# 1_Power.net
KiCad netlist of a schematic drawn in Altium Designer
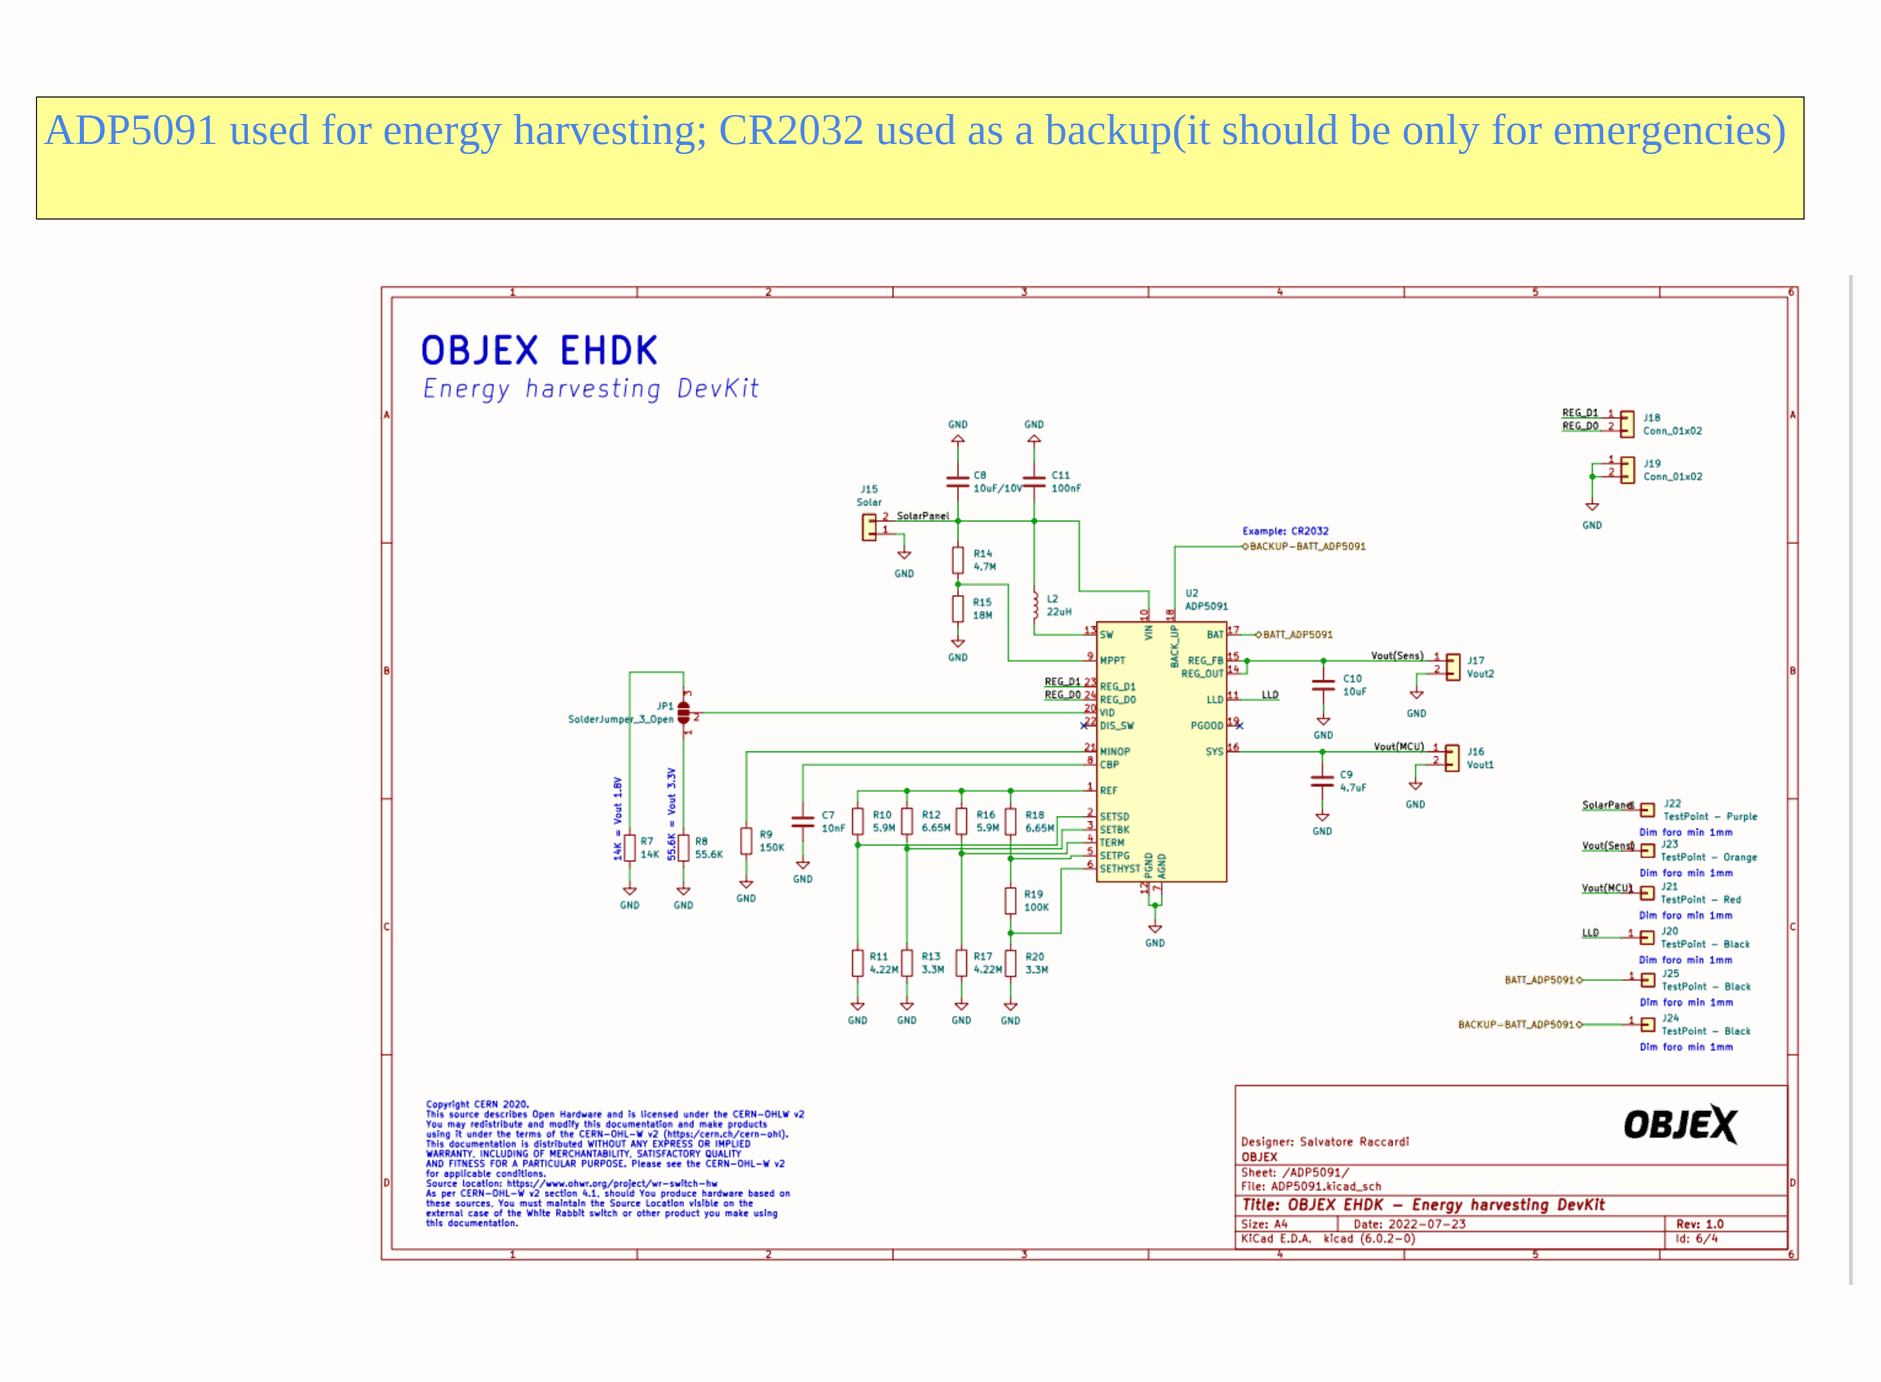
[diagram p0: 1_Power.SchDoc, left]
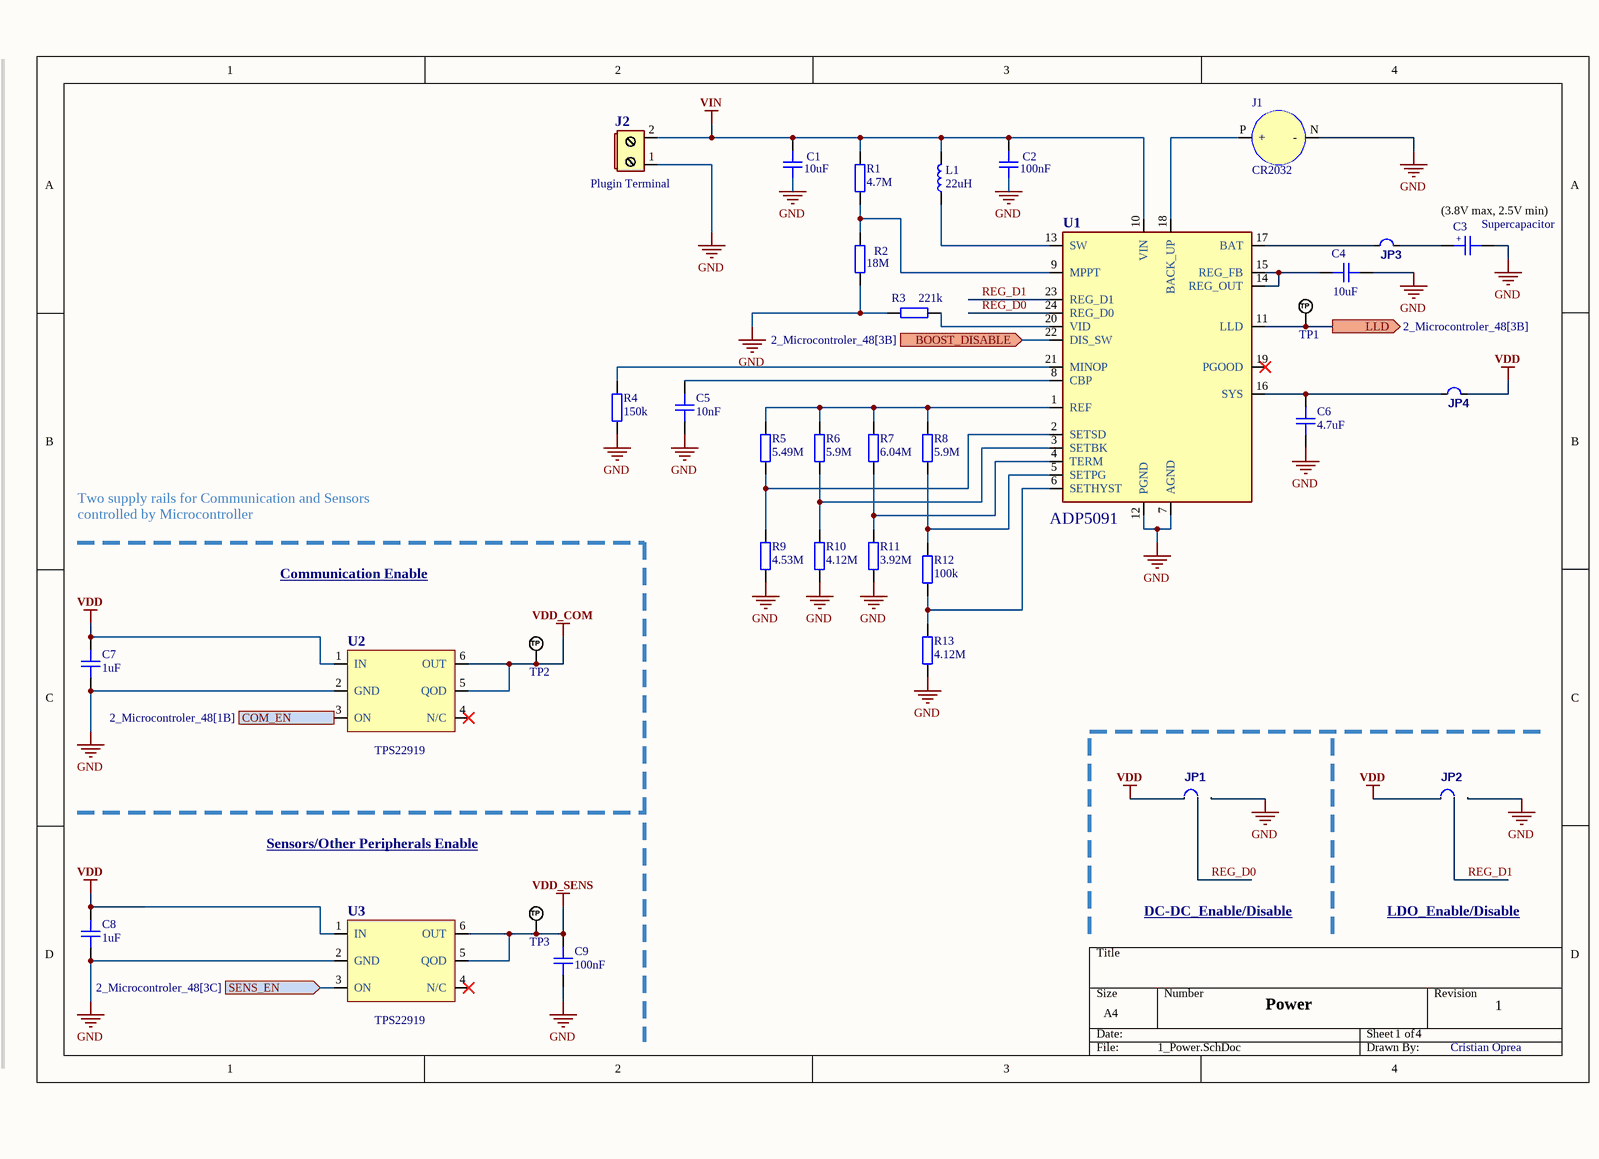
[diagram p1: 1_Power.SchDoc, middle]
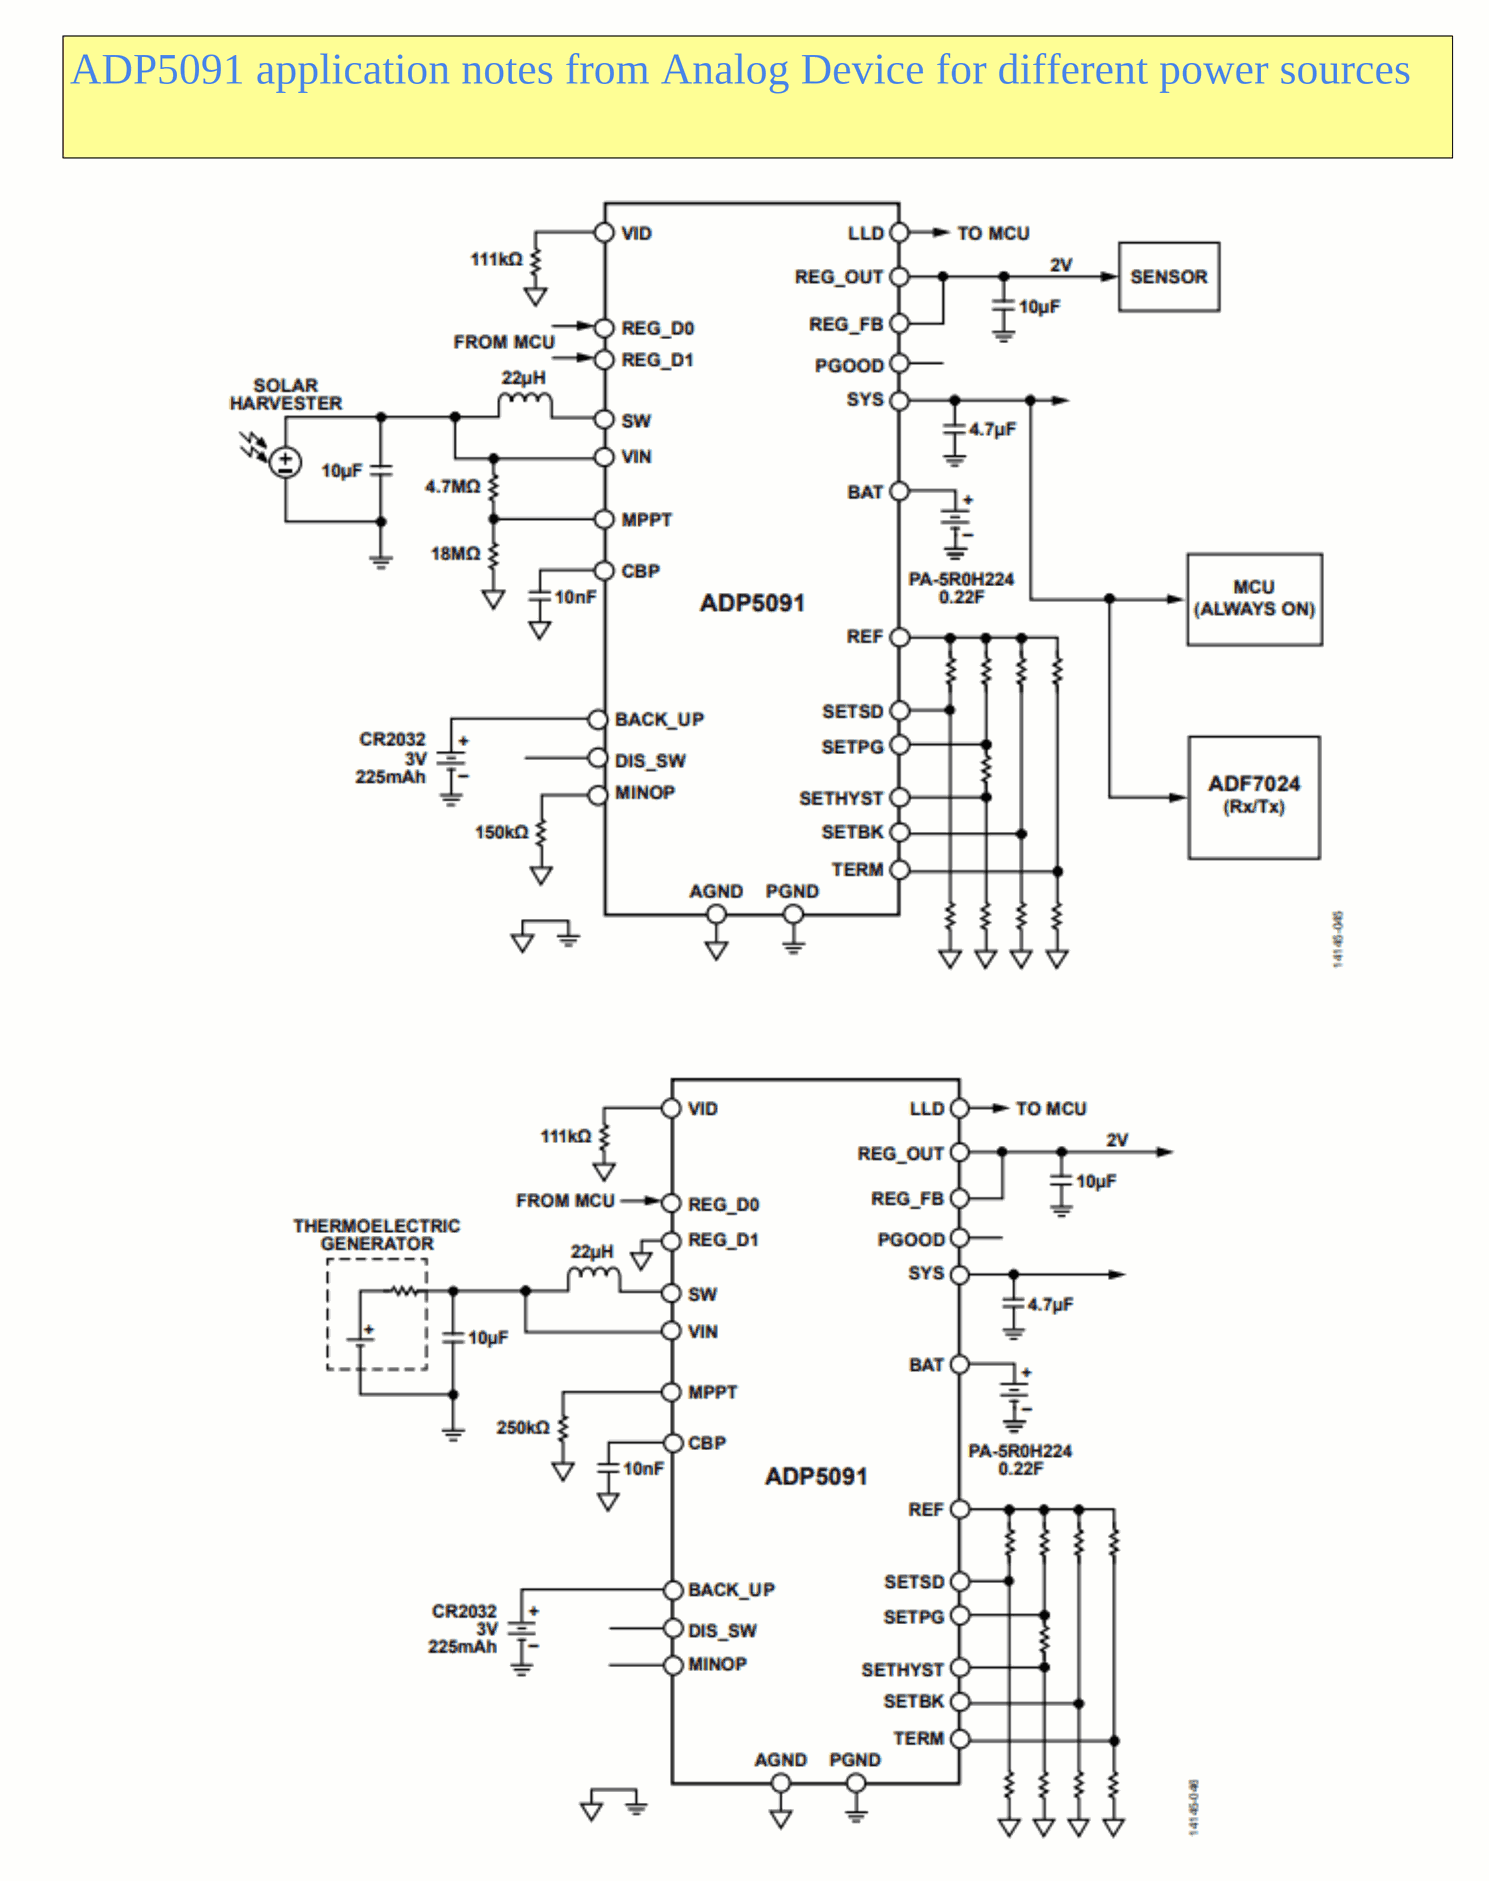
[diagram p2: 1_Power.SchDoc, right]

(export (version "E")
  (design (tool "Eeschema 10.0.6"))
  (components
    (comp (ref "C1")
      (value "10uF")
      (footprint "C0603")
      (description "Capacitor SMD 0603")
      (libsource (lib "Schlib_H2") (part "CAP_0603"))
    )
    (comp (ref "C2")
      (value "100nF")
      (footprint "C0603")
      (description "Capacitor SMD 0603")
      (libsource (lib "Schlib_H2") (part "CAP_0603"))
    )
    (comp (ref "C3")
      (value "Supercapacitor")
      (footprint "CAP_POL_8x16x3.5")
      (libsource (lib "Schlib_H2") (part "Supercapacitor"))
    )
    (comp (ref "C4")
      (value "10uF")
      (footprint "C0603")
      (description "Capacitor SMD 0603")
      (libsource (lib "Schlib_H2") (part "CAP_0603"))
    )
    (comp (ref "C5")
      (value "10nF")
      (footprint "C0603")
      (description "Capacitor SMD 0603")
      (libsource (lib "Schlib_H2") (part "CAP_0603"))
    )
    (comp (ref "C6")
      (value "4.7uF")
      (footprint "C0603")
      (description "Capacitor SMD 0603")
      (libsource (lib "Schlib_H2") (part "CAP_0603"))
    )
    (comp (ref "C7")
      (value "1uF")
      (footprint "C0603")
      (description "Capacitor SMD 0603")
      (libsource (lib "Schlib_H2") (part "CAP_0603"))
    )
    (comp (ref "C8")
      (value "1uF")
      (footprint "C0603")
      (description "Capacitor SMD 0603")
      (libsource (lib "Schlib_H2") (part "CAP_0603"))
    )
    (comp (ref "C9")
      (value "100nF")
      (footprint "C0603")
      (description "Capacitor SMD 0603")
      (libsource (lib "Schlib_H2") (part "CAP_0603"))
    )
    (comp (ref "J1")
      (value "CR2032")
      (footprint "BAT_CR2032-BS-6-1")
      (description "CR2032 Coin Cell Battery Holder")
      (fields (field (name "MANUFACTURER") "Q&J") (field (name "MANUFACTURER PART NUMBER") "CR2032-BS-6-1"))
      (libsource (lib "Schlib_H2") (part "CR2032-BS-6-1"))
    )
    (comp (ref "J2")
      (value "Plugin Terminal")
      (footprint "2.54_pluggable_terminal")
      (description "Screw terminal or plug terminal for power")
      (libsource (lib "Schlib_H2") (part "Power_Connector"))
    )
    (comp (ref "JP1")
      (value "JUMPER_3PIN")
      (footprint "HEADER_1x3_2.54")
      (libsource (lib "Schlib_H2") (part "JUMPER_3PIN"))
    )
    (comp (ref "JP2")
      (value "JUMPER_3PIN")
      (footprint "HEADER_1x3_2.54")
      (libsource (lib "Schlib_H2") (part "JUMPER_3PIN"))
    )
    (comp (ref "JP3")
      (value "JUMPER")
      (footprint "HEADER_1x2_2.54")
      (libsource (lib "Schlib_H2") (part "JUMPER"))
    )
    (comp (ref "JP4")
      (value "JUMPER")
      (footprint "HEADER_1x2_2.54")
      (libsource (lib "Schlib_H2") (part "JUMPER"))
    )
    (comp (ref "L1")
      (value "22uH")
      (footprint "IND_3.2_4")
      (description "Inductor SMD 1008")
      (libsource (lib "Schlib_H2") (part "IND_1008"))
    )
    (comp (ref "R1")
      (value "4.7M")
      (footprint "R0603")
      (description "Resistor SMD 0603")
      (libsource (lib "Schlib_H2") (part "RES_0603"))
    )
    (comp (ref "R2")
      (value "18M")
      (footprint "R0603")
      (description "Resistor SMD 0603")
      (libsource (lib "Schlib_H2") (part "RES_0603"))
    )
    (comp (ref "R3")
      (value "221k")
      (footprint "R0603")
      (description "Resistor SMD 0603")
      (libsource (lib "Schlib_H2") (part "RES_0603"))
    )
    (comp (ref "R4")
      (value "150k")
      (footprint "R0603")
      (description "Resistor SMD 0603")
      (libsource (lib "Schlib_H2") (part "RES_0603"))
    )
    (comp (ref "R5")
      (value "5.49M")
      (footprint "R0603")
      (description "Resistor SMD 0603")
      (libsource (lib "Schlib_H2") (part "RES_0603"))
    )
    (comp (ref "R6")
      (value "5.9M")
      (footprint "R0603")
      (description "Resistor SMD 0603")
      (libsource (lib "Schlib_H2") (part "RES_0603"))
    )
    (comp (ref "R7")
      (value "6.04M")
      (footprint "R0603")
      (description "Resistor SMD 0603")
      (libsource (lib "Schlib_H2") (part "RES_0603"))
    )
    (comp (ref "R8")
      (value "5.9M")
      (footprint "R0603")
      (description "Resistor SMD 0603")
      (libsource (lib "Schlib_H2") (part "RES_0603"))
    )
    (comp (ref "R9")
      (value "4.53M")
      (footprint "R0603")
      (description "Resistor SMD 0603")
      (libsource (lib "Schlib_H2") (part "RES_0603"))
    )
    (comp (ref "R10")
      (value "4.12M")
      (footprint "R0603")
      (description "Resistor SMD 0603")
      (libsource (lib "Schlib_H2") (part "RES_0603"))
    )
    (comp (ref "R11")
      (value "3.92M")
      (footprint "R0603")
      (description "Resistor SMD 0603")
      (libsource (lib "Schlib_H2") (part "RES_0603"))
    )
    (comp (ref "R12")
      (value "100k")
      (footprint "R0603")
      (description "Resistor SMD 0603")
      (libsource (lib "Schlib_H2") (part "RES_0603"))
    )
    (comp (ref "R13")
      (value "4.12M")
      (footprint "R0603")
      (description "Resistor SMD 0603")
      (libsource (lib "Schlib_H2") (part "RES_0603"))
    )
    (comp (ref "TP1")
      (value "TP_NOBOM")
      (footprint "TEST_PAD_THD")
      (description "Test Point Round 1mm (NO BOM)")
      (libsource (lib "Schlib_H2") (part "TEST_POINT_RND_1MM"))
    )
    (comp (ref "TP2")
      (value "TP_NOBOM")
      (footprint "TEST_PAD_THD")
      (description "Test Point Round 1mm (NO BOM)")
      (libsource (lib "Schlib_H2") (part "TEST_POINT_RND_1MM"))
    )
    (comp (ref "TP3")
      (value "TP_NOBOM")
      (footprint "TEST_PAD_THD")
      (description "Test Point Round 1mm (NO BOM)")
      (libsource (lib "Schlib_H2") (part "TEST_POINT_RND_1MM"))
    )
    (comp (ref "U1")
      (value "ADP5091")
      (footprint "LFCSP-24")
      (description "Ultralow Power Energy Harvester PMUs \r\nwith MPPT and Charge Management and BAckup Supply")
      (libsource (lib "Schlib_H2") (part "ADP5091"))
    )
    (comp (ref "U2")
      (value "TPS22919")
      (footprint "SC70-6")
      (description "5.5-V, 1.5-A, 90-mΩ load switch with adjustable output discharge")
      (libsource (lib "Schlib_H2") (part "TPS22919"))
    )
    (comp (ref "U3")
      (value "TPS22919")
      (footprint "SC70-6")
      (description "5.5-V, 1.5-A, 90-mΩ load switch with adjustable output discharge")
      (libsource (lib "Schlib_H2") (part "TPS22919"))
    )
  )
  (nets
    (net (code "1") (name "/BOOST_DISABLE") (class "Default")
      (node (ref "U1") (pin "22") (pinfunction "DIS_SW_22") (pintype "passive"))
    )
    (net (code "2") (name "/COM_EN") (class "Default")
      (node (ref "U2") (pin "3") (pinfunction "ON_3") (pintype "passive"))
    )
    (net (code "3") (name "/LLD") (class "Default")
      (node (ref "TP1") (pin "1") (pinfunction "TP_1") (pintype "passive"))
      (node (ref "U1") (pin "11") (pinfunction "LLD_11") (pintype "passive"))
    )
    (net (code "4") (name "/REG_D0") (class "Default")
      (node (ref "JP1") (pin "2") (pinfunction "2_2") (pintype "passive"))
      (node (ref "U1") (pin "24") (pinfunction "REG_D0_24") (pintype "passive"))
    )
    (net (code "5") (name "/REG_D1") (class "Default")
      (node (ref "JP2") (pin "2") (pinfunction "2_2") (pintype "passive"))
      (node (ref "U1") (pin "23") (pinfunction "REG_D1_23") (pintype "passive"))
    )
    (net (code "6") (name "/SENS_EN") (class "Default")
      (node (ref "U3") (pin "3") (pinfunction "ON_3") (pintype "passive"))
    )
    (net (code "7") (name "GND") (class "Default")
      (node (ref "C1") (pin "1") (pinfunction "1_1") (pintype "passive"))
      (node (ref "C2") (pin "1") (pinfunction "1_1") (pintype "passive"))
      (node (ref "C3") (pin "2") (pinfunction "2_2") (pintype "passive"))
      (node (ref "C4") (pin "2") (pinfunction "2_2") (pintype "passive"))
      (node (ref "C5") (pin "1") (pinfunction "1_1") (pintype "passive"))
      (node (ref "C6") (pin "1") (pinfunction "1_1") (pintype "passive"))
      (node (ref "C7") (pin "1") (pinfunction "1_1") (pintype "passive"))
      (node (ref "C8") (pin "1") (pinfunction "1_1") (pintype "passive"))
      (node (ref "C9") (pin "1") (pinfunction "1_1") (pintype "passive"))
      (node (ref "J1") (pin "N") (pinfunction "-_N") (pintype "passive"))
      (node (ref "J2") (pin "1") (pinfunction "1_1") (pintype "passive"))
      (node (ref "JP1") (pin "3") (pinfunction "3_3") (pintype "passive"))
      (node (ref "JP2") (pin "3") (pinfunction "3_3") (pintype "passive"))
      (node (ref "R10") (pin "1") (pinfunction "1_1") (pintype "passive"))
      (node (ref "R11") (pin "1") (pinfunction "1_1") (pintype "passive"))
      (node (ref "R13") (pin "1") (pinfunction "1_1") (pintype "passive"))
      (node (ref "R2") (pin "1") (pinfunction "1_1") (pintype "passive"))
      (node (ref "R3") (pin "1") (pinfunction "1_1") (pintype "passive"))
      (node (ref "R4") (pin "1") (pinfunction "1_1") (pintype "passive"))
      (node (ref "R9") (pin "1") (pinfunction "1_1") (pintype "passive"))
      (node (ref "U1") (pin "12") (pinfunction "PGND_12") (pintype "passive"))
      (node (ref "U1") (pin "7") (pinfunction "AGND_7") (pintype "passive"))
      (node (ref "U2") (pin "2") (pinfunction "GND_2") (pintype "passive"))
      (node (ref "U3") (pin "2") (pinfunction "GND_2") (pintype "passive"))
    )
    (net (code "8") (name "Net-(C3-Pad1)") (class "Default")
      (node (ref "C3") (pin "1") (pinfunction "1_1") (pintype "passive"))
      (node (ref "JP3") (pin "2") (pinfunction "2_2") (pintype "passive"))
    )
    (net (code "9") (name "Net-(J1-+)") (class "Default")
      (node (ref "J1") (pin "P") (pinfunction "+_P") (pintype "passive"))
      (node (ref "U1") (pin "18") (pinfunction "BACK_UP_18") (pintype "passive"))
    )
    (net (code "10") (name "Net-(U1-BAT)") (class "Default")
      (node (ref "JP3") (pin "1") (pinfunction "1_1") (pintype "passive"))
      (node (ref "U1") (pin "17") (pinfunction "BAT_17") (pintype "passive"))
    )
    (net (code "11") (name "Net-(U1-CBP)") (class "Default")
      (node (ref "C5") (pin "2") (pinfunction "2_2") (pintype "passive"))
      (node (ref "U1") (pin "8") (pinfunction "CBP_8") (pintype "passive"))
    )
    (net (code "12") (name "Net-(U1-MINOP)") (class "Default")
      (node (ref "R4") (pin "2") (pinfunction "2_2") (pintype "passive"))
      (node (ref "U1") (pin "21") (pinfunction "MINOP_21") (pintype "passive"))
    )
    (net (code "13") (name "Net-(U1-MPPT)") (class "Default")
      (node (ref "R1") (pin "1") (pinfunction "1_1") (pintype "passive"))
      (node (ref "R2") (pin "2") (pinfunction "2_2") (pintype "passive"))
      (node (ref "U1") (pin "9") (pinfunction "MPPT_9") (pintype "passive"))
    )
    (net (code "14") (name "Net-(U1-REF)") (class "Default")
      (node (ref "R5") (pin "2") (pinfunction "2_2") (pintype "passive"))
      (node (ref "R6") (pin "2") (pinfunction "2_2") (pintype "passive"))
      (node (ref "R7") (pin "2") (pinfunction "2_2") (pintype "passive"))
      (node (ref "R8") (pin "2") (pinfunction "2_2") (pintype "passive"))
      (node (ref "U1") (pin "1") (pinfunction "REF_1") (pintype "passive"))
    )
    (net (code "15") (name "Net-(U1-REG_FB)") (class "Default")
      (node (ref "C4") (pin "1") (pinfunction "1_1") (pintype "passive"))
      (node (ref "U1") (pin "14") (pinfunction "REG_OUT_14") (pintype "passive"))
      (node (ref "U1") (pin "15") (pinfunction "REG_FB_15") (pintype "passive"))
    )
    (net (code "16") (name "Net-(U1-SETBK)") (class "Default")
      (node (ref "R10") (pin "2") (pinfunction "2_2") (pintype "passive"))
      (node (ref "R6") (pin "1") (pinfunction "1_1") (pintype "passive"))
      (node (ref "U1") (pin "3") (pinfunction "SETBK_3") (pintype "passive"))
    )
    (net (code "17") (name "Net-(U1-SETHYST)") (class "Default")
      (node (ref "R12") (pin "1") (pinfunction "1_1") (pintype "passive"))
      (node (ref "R13") (pin "2") (pinfunction "2_2") (pintype "passive"))
      (node (ref "U1") (pin "6") (pinfunction "SETHYST_6") (pintype "passive"))
    )
    (net (code "18") (name "Net-(U1-SETPG)") (class "Default")
      (node (ref "R12") (pin "2") (pinfunction "2_2") (pintype "passive"))
      (node (ref "R8") (pin "1") (pinfunction "1_1") (pintype "passive"))
      (node (ref "U1") (pin "5") (pinfunction "SETPG_5") (pintype "passive"))
    )
    (net (code "19") (name "Net-(U1-SETSD)") (class "Default")
      (node (ref "R5") (pin "1") (pinfunction "1_1") (pintype "passive"))
      (node (ref "R9") (pin "2") (pinfunction "2_2") (pintype "passive"))
      (node (ref "U1") (pin "2") (pinfunction "SETSD_2") (pintype "passive"))
    )
    (net (code "20") (name "Net-(U1-SW)") (class "Default")
      (node (ref "L1") (pin "1") (pinfunction "1_1") (pintype "passive"))
      (node (ref "U1") (pin "13") (pinfunction "SW_13") (pintype "passive"))
    )
    (net (code "21") (name "Net-(U1-SYS)") (class "Default")
      (node (ref "C6") (pin "2") (pinfunction "2_2") (pintype "passive"))
      (node (ref "JP4") (pin "1") (pinfunction "1_1") (pintype "passive"))
      (node (ref "U1") (pin "16") (pinfunction "SYS_16") (pintype "passive"))
    )
    (net (code "22") (name "Net-(U1-TERM)") (class "Default")
      (node (ref "R11") (pin "2") (pinfunction "2_2") (pintype "passive"))
      (node (ref "R7") (pin "1") (pinfunction "1_1") (pintype "passive"))
      (node (ref "U1") (pin "4") (pinfunction "TERM_4") (pintype "passive"))
    )
    (net (code "23") (name "Net-(U1-VID)") (class "Default")
      (node (ref "R3") (pin "2") (pinfunction "2_2") (pintype "passive"))
      (node (ref "U1") (pin "20") (pinfunction "VID_20") (pintype "passive"))
    )
    (net (code "24") (name "VDD") (class "Default")
      (node (ref "C7") (pin "2") (pinfunction "2_2") (pintype "passive"))
      (node (ref "C8") (pin "2") (pinfunction "2_2") (pintype "passive"))
      (node (ref "JP1") (pin "1") (pinfunction "1_1") (pintype "passive"))
      (node (ref "JP2") (pin "1") (pinfunction "1_1") (pintype "passive"))
      (node (ref "JP4") (pin "2") (pinfunction "2_2") (pintype "passive"))
      (node (ref "U2") (pin "1") (pinfunction "IN_1") (pintype "passive"))
      (node (ref "U3") (pin "1") (pinfunction "IN_1") (pintype "passive"))
    )
    (net (code "25") (name "VDD_COM") (class "Default")
      (node (ref "TP2") (pin "1") (pinfunction "TP_1") (pintype "passive"))
      (node (ref "U2") (pin "5") (pinfunction "QOD_5") (pintype "passive"))
      (node (ref "U2") (pin "6") (pinfunction "OUT_6") (pintype "passive"))
    )
    (net (code "26") (name "VDD_SENS") (class "Default")
      (node (ref "C9") (pin "2") (pinfunction "2_2") (pintype "passive"))
      (node (ref "TP3") (pin "1") (pinfunction "TP_1") (pintype "passive"))
      (node (ref "U3") (pin "5") (pinfunction "QOD_5") (pintype "passive"))
      (node (ref "U3") (pin "6") (pinfunction "OUT_6") (pintype "passive"))
    )
    (net (code "27") (name "VIN") (class "Default")
      (node (ref "C1") (pin "2") (pinfunction "2_2") (pintype "passive"))
      (node (ref "C2") (pin "2") (pinfunction "2_2") (pintype "passive"))
      (node (ref "J2") (pin "2") (pinfunction "2_2") (pintype "passive"))
      (node (ref "L1") (pin "2") (pinfunction "2_2") (pintype "passive"))
      (node (ref "R1") (pin "2") (pinfunction "2_2") (pintype "passive"))
      (node (ref "U1") (pin "10") (pinfunction "VIN_10") (pintype "passive"))
    )
    (net (code "28") (name "unconnected-(U1-PGOOD-Pad19)") (class "Default")
      (node (ref "U1") (pin "19") (pinfunction "PGOOD_19") (pintype "passive+no_connect"))
    )
    (net (code "29") (name "unconnected-(U2-N{slash}C-Pad4)") (class "Default")
      (node (ref "U2") (pin "4") (pinfunction "N/C_4") (pintype "passive+no_connect"))
    )
    (net (code "30") (name "unconnected-(U3-N{slash}C-Pad4)") (class "Default")
      (node (ref "U3") (pin "4") (pinfunction "N/C_4") (pintype "passive+no_connect"))
    )
  )
)
